# ir_upgrade.net
KiCad netlist of a schematic drawn in EAGLE
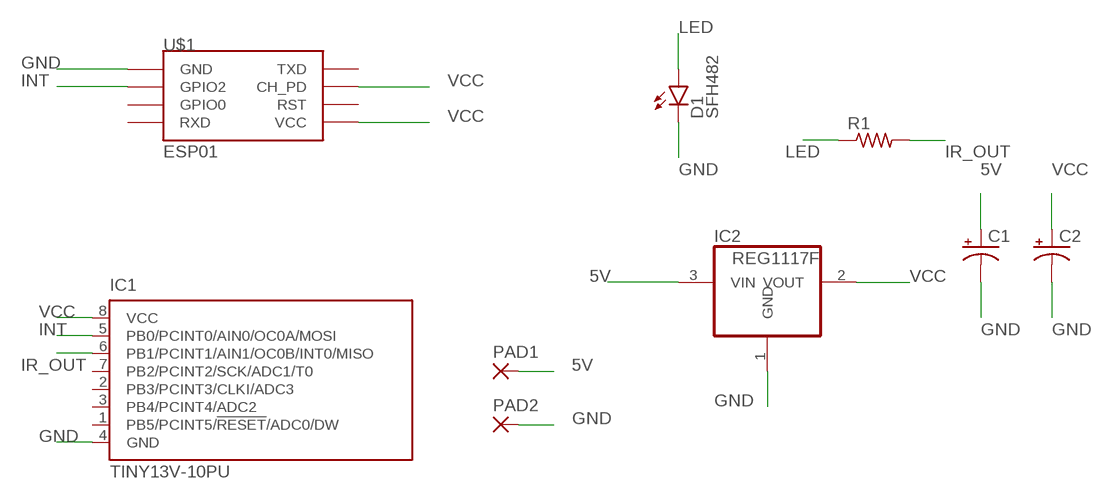
[diagram p0: schematic, sheet 1]

(export (version "E")
  (design (tool "Eeschema 10.0.6"))
  (components
    (comp (ref "C1")
      (value "CPOL-USTT5D7")
      (footprint "eagle-import:TT5D7")
      (libsource (lib "eagle-import") (part "CPOL-USTT5D7"))
    )
    (comp (ref "C2")
      (value "CPOL-USTT5D7")
      (footprint "eagle-import:TT5D7")
      (libsource (lib "eagle-import") (part "CPOL-USTT5D7"))
    )
    (comp (ref "D1")
      (value "SFH482")
      (footprint "eagle-import:SFH482")
      (libsource (lib "eagle-import") (part "SFH482"))
    )
    (comp (ref "IC1")
      (value "TINY13V-10PU")
      (footprint "eagle-import:DIL08")
      (fields (field (name "MPN") "ATTINY13V-10PU"))
      (libsource (lib "eagle-import") (part "TINY13PUV-10"))
    )
    (comp (ref "IC2")
      (value "REG1117F")
      (footprint "eagle-import:DD-3")
      (fields (field (name "MF") "TEXAS INSTRUMENTS") (field (name "MPN") "REG1117FAKTTT"))
      (libsource (lib "eagle-import") (part "REG1117F"))
    )
    (comp (ref "PAD1")
      (value "2,15/1,0")
      (footprint "eagle-import:2,15_1,0")
      (libsource (lib "eagle-import") (part "2,15/1,0"))
    )
    (comp (ref "PAD2")
      (value "2,15/1,0")
      (footprint "eagle-import:2,15_1,0")
      (libsource (lib "eagle-import") (part "2,15/1,0"))
    )
    (comp (ref "R1")
      (value "R-US_VMTA55")
      (footprint "eagle-import:VMTA55")
      (libsource (lib "eagle-import") (part "R-US_VMTA55"))
    )
    (comp (ref "U$1")
      (value "ESP01")
      (footprint "eagle-import:ESP01")
      (libsource (lib "eagle-import") (part "ESP01"))
    )
  )
  (nets
    (net (code "1") (name "/5V") (class "Default")
      (node (ref "C1") (pin "+") (pinfunction "+_+") (pintype "passive"))
      (node (ref "IC2") (pin "3") (pinfunction "VIN_3") (pintype "input"))
      (node (ref "PAD1") (pin "1") (pinfunction "P_1") (pintype "passive"))
    )
    (net (code "2") (name "/GND") (class "Default")
      (node (ref "C1") (pin "-") (pinfunction "-_-") (pintype "passive"))
      (node (ref "C2") (pin "-") (pinfunction "-_-") (pintype "passive"))
      (node (ref "D1") (pin "K") (pinfunction "C_K") (pintype "passive"))
      (node (ref "IC1") (pin "4") (pinfunction "GND_4") (pintype "power_in"))
      (node (ref "IC2") (pin "1") (pinfunction "GND_1") (pintype "power_in"))
      (node (ref "PAD2") (pin "1") (pinfunction "P_1") (pintype "passive"))
      (node (ref "U$1") (pin "GND") (pinfunction "GND_GND") (pintype "bidirectional"))
    )
    (net (code "3") (name "/INT") (class "Default")
      (node (ref "IC1") (pin "5") (pinfunction "PB0/PCINT0/AIN0/OC0A/MOSI_5") (pintype "bidirectional"))
      (node (ref "U$1") (pin "GPIO2") (pinfunction "GPIO2_GPIO2") (pintype "bidirectional"))
    )
    (net (code "4") (name "/IR_OUT") (class "Default")
      (node (ref "IC1") (pin "6") (pinfunction "PB1/PCINT1/AIN1/OC0B/INT0/MISO_6") (pintype "bidirectional"))
      (node (ref "R1") (pin "2") (pinfunction "2_2") (pintype "passive"))
    )
    (net (code "5") (name "/LED") (class "Default")
      (node (ref "D1") (pin "A") (pinfunction "A_A") (pintype "passive"))
      (node (ref "R1") (pin "1") (pinfunction "1_1") (pintype "passive"))
    )
    (net (code "6") (name "/VCC") (class "Default")
      (node (ref "C2") (pin "+") (pinfunction "+_+") (pintype "passive"))
      (node (ref "IC1") (pin "8") (pinfunction "VCC_8") (pintype "power_in"))
      (node (ref "IC2") (pin "2") (pinfunction "VOUT_2") (pintype "output"))
      (node (ref "U$1") (pin "CH_PD") (pinfunction "CH_PD_CH_PD") (pintype "bidirectional"))
      (node (ref "U$1") (pin "VCC") (pinfunction "VCC_VCC") (pintype "bidirectional"))
    )
    (net (code "7") (name "unconnected-(IC1-PB2{slash}PCINT2{slash}SCK{slash}ADC1{slash}T0-Pad7)") (class "Default")
      (node (ref "IC1") (pin "7") (pinfunction "PB2/PCINT2/SCK/ADC1/T0_7") (pintype "bidirectional"))
    )
    (net (code "8") (name "unconnected-(IC1-PB3{slash}PCINT3{slash}CLKI{slash}ADC3-Pad2)") (class "Default")
      (node (ref "IC1") (pin "2") (pinfunction "PB3/PCINT3/CLKI/ADC3_2") (pintype "bidirectional"))
    )
    (net (code "9") (name "unconnected-(IC1-PB4{slash}PCINT4{slash}ADC2-Pad3)") (class "Default")
      (node (ref "IC1") (pin "3") (pinfunction "PB4/PCINT4/ADC2_3") (pintype "bidirectional"))
    )
    (net (code "10") (name "unconnected-(IC1-PB5{slash}PCINT5{slash}~{RESET}{slash}ADC0{slash}DW-Pad1)") (class "Default")
      (node (ref "IC1") (pin "1") (pinfunction "PB5/PCINT5/~{RESET}/ADC0/DW_1") (pintype "bidirectional"))
    )
    (net (code "11") (name "unconnected-(U$1-PadGPIO0)") (class "Default")
      (node (ref "U$1") (pin "GPIO0") (pinfunction "GPIO0_GPIO0") (pintype "bidirectional"))
    )
    (net (code "12") (name "unconnected-(U$1-PadRST)") (class "Default")
      (node (ref "U$1") (pin "RST") (pinfunction "RST_RST") (pintype "bidirectional"))
    )
    (net (code "13") (name "unconnected-(U$1-RXD-PadRX)") (class "Default")
      (node (ref "U$1") (pin "RX") (pinfunction "RXD_RX") (pintype "bidirectional"))
    )
    (net (code "14") (name "unconnected-(U$1-TXD-PadTX)") (class "Default")
      (node (ref "U$1") (pin "TX") (pinfunction "TXD_TX") (pintype "bidirectional"))
    )
  )
)
